# tick-mk-4_4.net
KiCad netlist of a schematic drawn in EAGLE
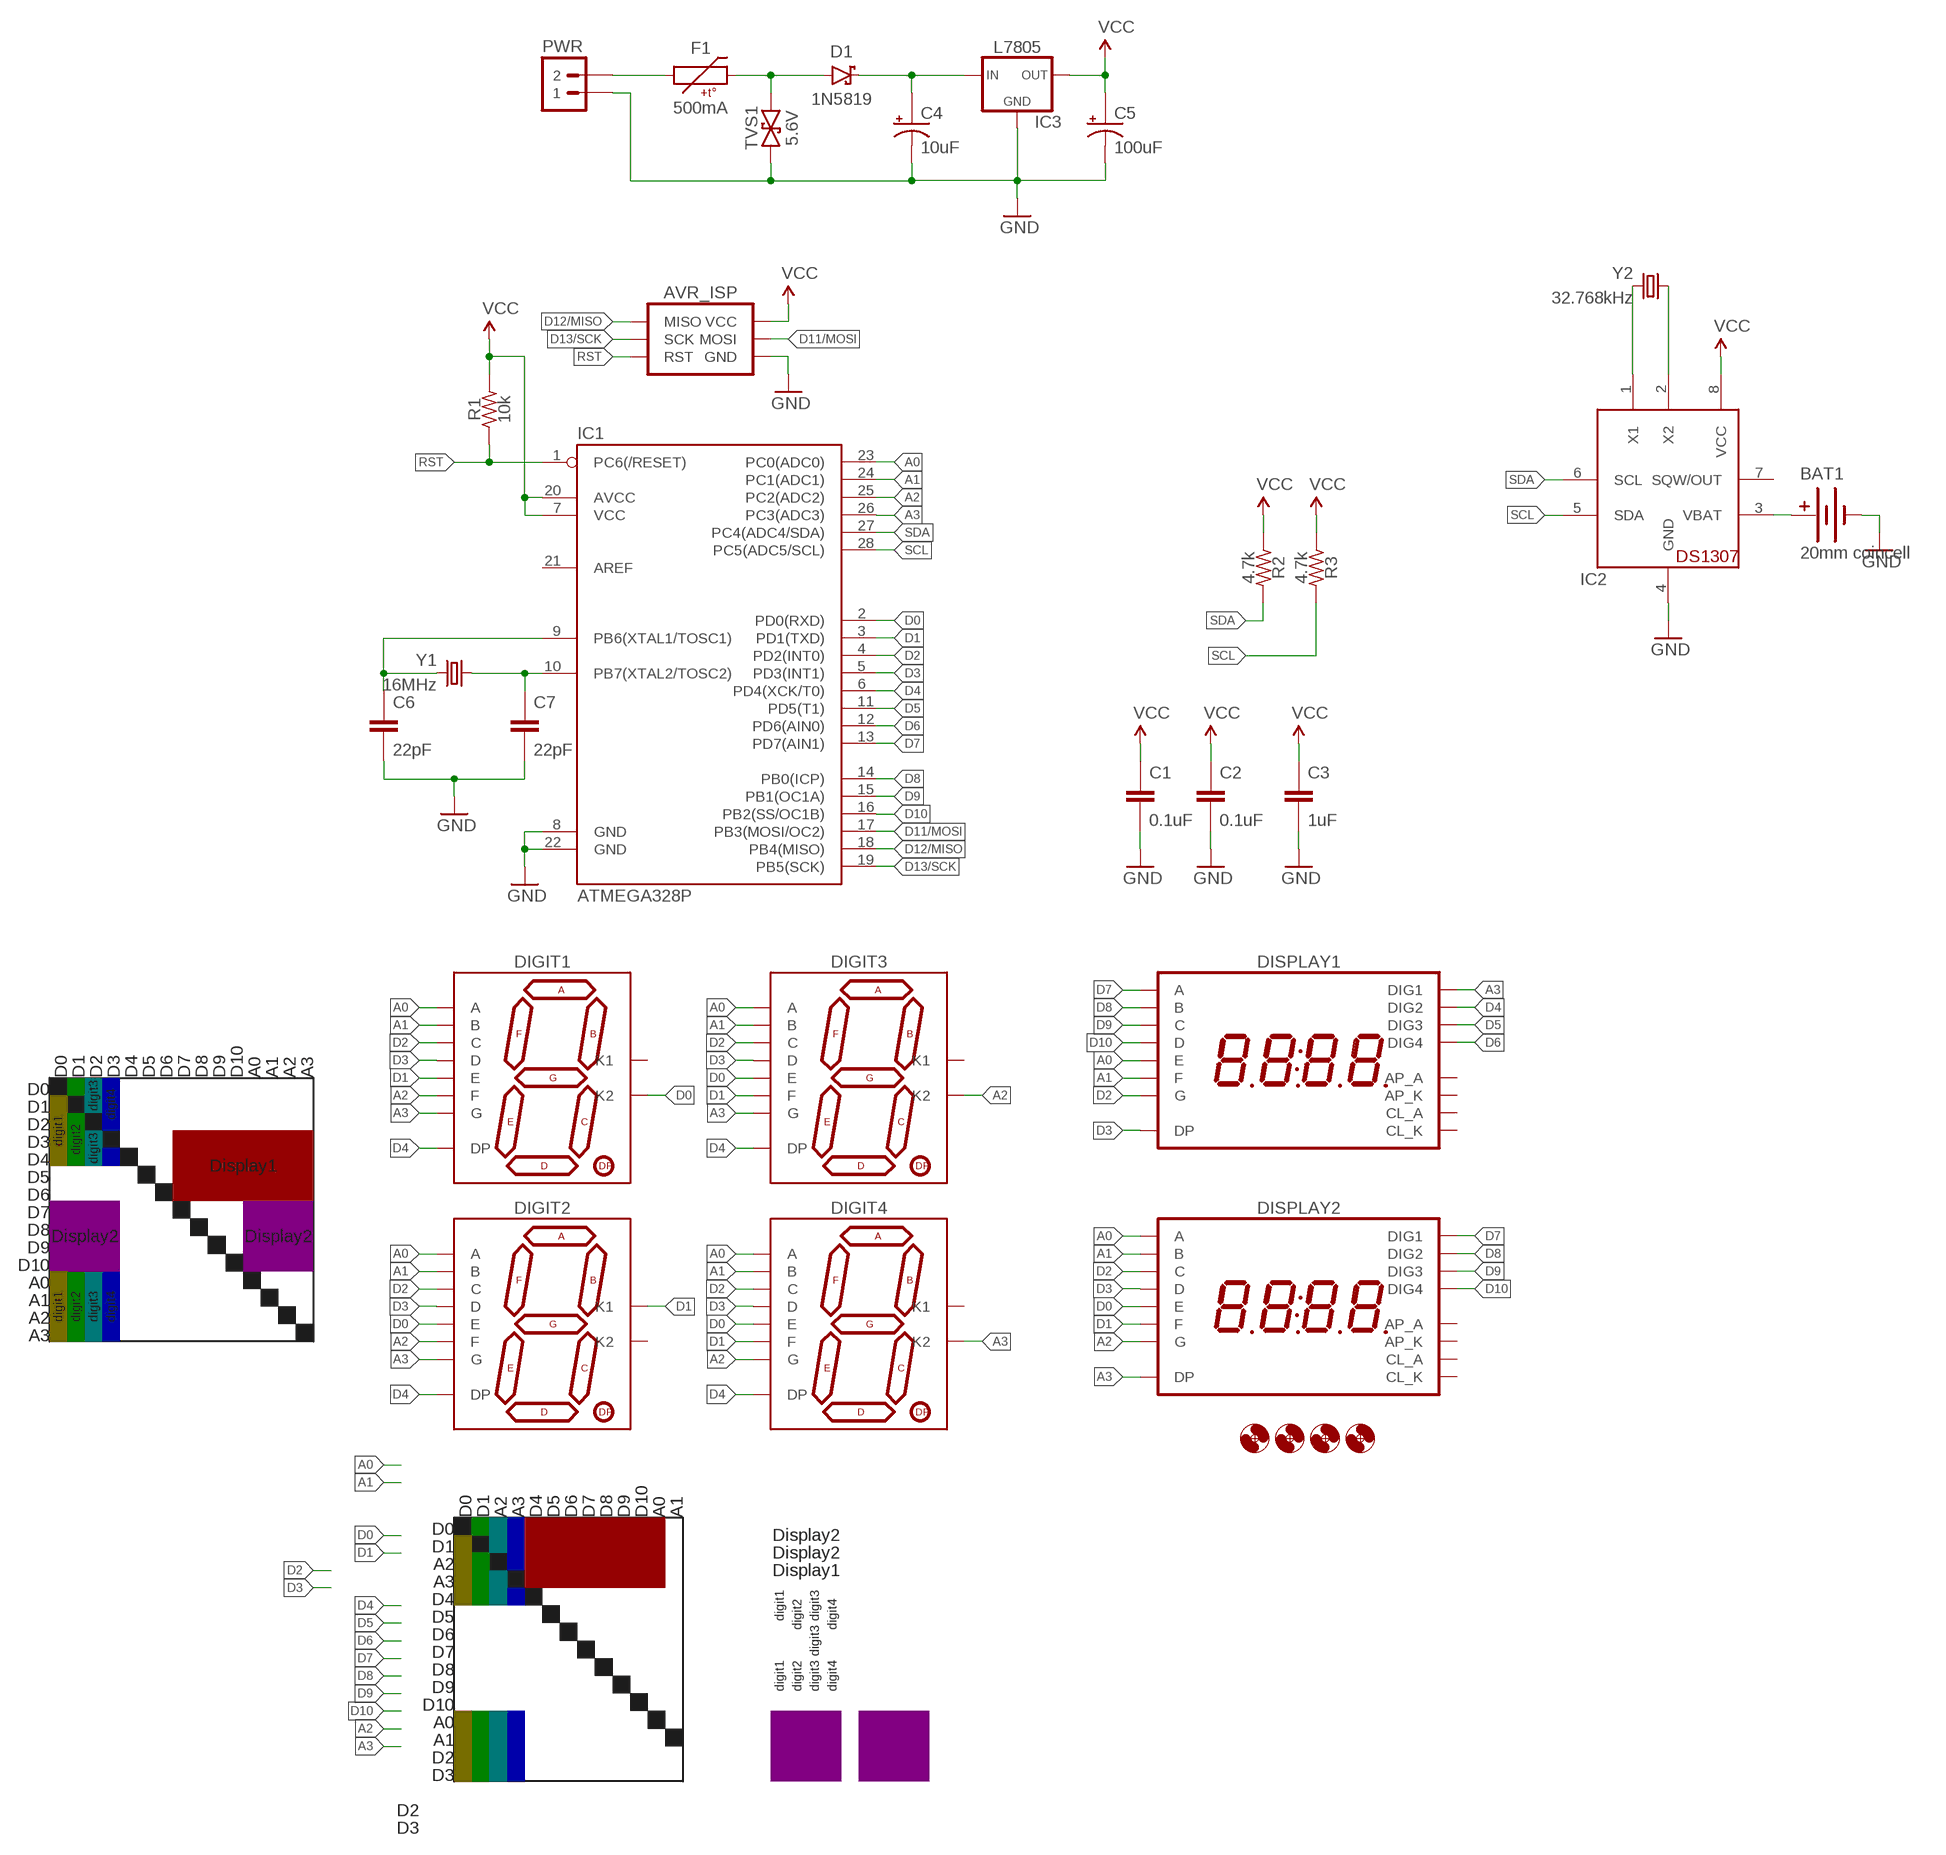
[diagram p0: schematic, sheet 1]

(export (version "E")
  (design (tool "Eeschema 10.0.6"))
  (components
    (comp (ref "AVR_ISP")
      (value "AVR_SPI_PRG_6PTH")
      (footprint "eagle-import:2X3")
      (libsource (lib "eagle-import") (part "AVR_SPI_PRG_6PTH"))
    )
    (comp (ref "BAT1")
      (value "20mm coincell")
      (footprint "eagle-import:BATTCON_20MM_MINE")
      (libsource (lib "eagle-import") (part "BATTERY20MMSMD-MINE"))
    )
    (comp (ref "C1")
      (value "0.1uF")
      (footprint "eagle-import:C025-024X044")
      (libsource (lib "eagle-import") (part "CAPACITOR-CERAMIC025-024X044"))
    )
    (comp (ref "C2")
      (value "0.1uF")
      (footprint "eagle-import:C025-024X044")
      (libsource (lib "eagle-import") (part "CAPACITOR-CERAMIC025-024X044"))
    )
    (comp (ref "C3")
      (value "1uF")
      (footprint "eagle-import:C025-024X044")
      (libsource (lib "eagle-import") (part "CAPACITOR-CERAMIC025-024X044"))
    )
    (comp (ref "C4")
      (value "10uF")
      (footprint "eagle-import:E2-5")
      (libsource (lib "eagle-import") (part "CAPACITOR-POLARIZEDE2-5"))
    )
    (comp (ref "C5")
      (value "100uF")
      (footprint "eagle-import:E2,5-6")
      (libsource (lib "eagle-import") (part "CAPACITOR-POLARIZEDE2.5-6"))
    )
    (comp (ref "C6")
      (value "22pF")
      (footprint "eagle-import:C025-024X044")
      (libsource (lib "eagle-import") (part "CAPACITOR-CERAMIC025-024X044"))
    )
    (comp (ref "C7")
      (value "22pF")
      (footprint "eagle-import:C025-024X044")
      (libsource (lib "eagle-import") (part "CAPACITOR-CERAMIC025-024X044"))
    )
    (comp (ref "D1")
      (value "1N5819")
      (footprint "eagle-import:DIODE-10.16MM")
      (libsource (lib "eagle-import") (part "DIODE-SCHOTTKYPTH-10.16MM"))
    )
    (comp (ref "DIGIT1")
      (value "7SEG_1DIGPTH-25.4MM-BARE")
      (footprint "eagle-import:7SEG_1DIG_25.4MM_NOSILK")
      (libsource (lib "eagle-import") (part "7SEG_1DIGPTH-25.4MM-BARE"))
    )
    (comp (ref "DIGIT2")
      (value "7SEG_1DIGPTH-25.4MM-BARE")
      (footprint "eagle-import:7SEG_1DIG_25.4MM_NOSILK")
      (libsource (lib "eagle-import") (part "7SEG_1DIGPTH-25.4MM-BARE"))
    )
    (comp (ref "DIGIT3")
      (value "7SEG_1DIGPTH-25.4MM-BARE")
      (footprint "eagle-import:7SEG_1DIG_25.4MM_NOSILK")
      (libsource (lib "eagle-import") (part "7SEG_1DIGPTH-25.4MM-BARE"))
    )
    (comp (ref "DIGIT4")
      (value "7SEG_1DIGPTH-25.4MM-BARE")
      (footprint "eagle-import:7SEG_1DIG_25.4MM_NOSILK")
      (libsource (lib "eagle-import") (part "7SEG_1DIGPTH-25.4MM-BARE"))
    )
    (comp (ref "DISPLAY1")
      (value "7SEG_4DIGIT_COLON_APOS")
      (footprint "eagle-import:7SEG_4DIG_10MM")
      (libsource (lib "eagle-import") (part "7SEG_4DIGIT_COLON_APOS"))
    )
    (comp (ref "DISPLAY2")
      (value "7SEG_4DIGIT_COLON_APOS")
      (footprint "eagle-import:7SEG_4DIG_10MM")
      (libsource (lib "eagle-import") (part "7SEG_4DIGIT_COLON_APOS"))
    )
    (comp (ref "F1")
      (value "500mA")
      (footprint "eagle-import:PTC-PTH-5.08MM")
      (libsource (lib "eagle-import") (part "PTCPTH-5.08MM"))
    )
    (comp (ref "H1")
      (value "HOLE#2")
      (footprint "eagle-import:HOLE-#2")
      (libsource (lib "eagle-import") (part "HOLE#2"))
    )
    (comp (ref "H2")
      (value "HOLE#2")
      (footprint "eagle-import:HOLE-#2")
      (libsource (lib "eagle-import") (part "HOLE#2"))
    )
    (comp (ref "H3")
      (value "HOLE#2")
      (footprint "eagle-import:HOLE-#2")
      (libsource (lib "eagle-import") (part "HOLE#2"))
    )
    (comp (ref "H4")
      (value "HOLE#2")
      (footprint "eagle-import:HOLE-#2")
      (libsource (lib "eagle-import") (part "HOLE#2"))
    )
    (comp (ref "IC1")
      (value "ATMEGA328P")
      (footprint "eagle-import:DIL28-3")
      (libsource (lib "eagle-import") (part "ATMEGA328P_PDIP"))
    )
    (comp (ref "IC2")
      (value "DS1307")
      (footprint "eagle-import:DIL08")
      (libsource (lib "eagle-import") (part "DS1307"))
    )
    (comp (ref "IC3")
      (value "L7805")
      (footprint "eagle-import:TO220-IGO-THERMPAD")
      (libsource (lib "eagle-import") (part "V_REG_78XXTO-220-THERMPAD"))
    )
    (comp (ref "PWR")
      (value "M02JST-PTH-VERT")
      (footprint "eagle-import:JST-2-PH-VERT-PTH")
      (libsource (lib "eagle-import") (part "M02JST-PTH-VERT"))
    )
    (comp (ref "R1")
      (value "10k")
      (footprint "eagle-import:RESISTOR-AXIAL-PTH-7.62MM")
      (libsource (lib "eagle-import") (part "RESISTORPTH-AXIAL-7.62MM"))
    )
    (comp (ref "R2")
      (value "4.7k")
      (footprint "eagle-import:RESISTOR-AXIAL-PTH-7.62MM")
      (libsource (lib "eagle-import") (part "RESISTORPTH-AXIAL-7.62MM"))
    )
    (comp (ref "R3")
      (value "4.7k")
      (footprint "eagle-import:RESISTOR-AXIAL-PTH-7.62MM")
      (libsource (lib "eagle-import") (part "RESISTORPTH-AXIAL-7.62MM"))
    )
    (comp (ref "TVS1")
      (value "5.6V")
      (footprint "eagle-import:DO-41-TVS-BI-10.16MM")
      (libsource (lib "eagle-import") (part "TVSDO-41-10.16MM"))
    )
    (comp (ref "Y1")
      (value "16MHz")
      (footprint "eagle-import:HC49U-V")
      (libsource (lib "eagle-import") (part "CRYSTALHC49UV"))
    )
    (comp (ref "Y2")
      (value "32.768kHz")
      (footprint "eagle-import:TC26H")
      (libsource (lib "eagle-import") (part "CRYSTALTC26H"))
    )
  )
  (nets
    (net (code "1") (name "A0") (class "Default")
      (node (ref "DIGIT1") (pin "7") (pinfunction "A_7") (pintype "bidirectional"))
      (node (ref "DIGIT2") (pin "7") (pinfunction "A_7") (pintype "bidirectional"))
      (node (ref "DIGIT3") (pin "7") (pinfunction "A_7") (pintype "bidirectional"))
      (node (ref "DIGIT4") (pin "7") (pinfunction "A_7") (pintype "bidirectional"))
      (node (ref "DISPLAY1") (pin "5") (pinfunction "E_5") (pintype "passive"))
      (node (ref "DISPLAY2") (pin "14") (pinfunction "A_14") (pintype "passive"))
      (node (ref "IC1") (pin "23") (pinfunction "PC0(ADC0)_23") (pintype "bidirectional"))
    )
    (net (code "2") (name "A1") (class "Default")
      (node (ref "DIGIT1") (pin "6") (pinfunction "B_6") (pintype "bidirectional"))
      (node (ref "DIGIT2") (pin "6") (pinfunction "B_6") (pintype "bidirectional"))
      (node (ref "DIGIT3") (pin "6") (pinfunction "B_6") (pintype "bidirectional"))
      (node (ref "DIGIT4") (pin "6") (pinfunction "B_6") (pintype "bidirectional"))
      (node (ref "DISPLAY1") (pin "11") (pinfunction "F_11") (pintype "passive"))
      (node (ref "DISPLAY2") (pin "16") (pinfunction "B_16") (pintype "passive"))
      (node (ref "IC1") (pin "24") (pinfunction "PC1(ADC1)_24") (pintype "bidirectional"))
    )
    (net (code "3") (name "A2") (class "Default")
      (node (ref "DIGIT1") (pin "9") (pinfunction "F_9") (pintype "bidirectional"))
      (node (ref "DIGIT2") (pin "9") (pinfunction "F_9") (pintype "bidirectional"))
      (node (ref "DIGIT3") (pin "8") (pinfunction "K2_8") (pintype "bidirectional"))
      (node (ref "DIGIT4") (pin "10") (pinfunction "G_10") (pintype "bidirectional"))
      (node (ref "DISPLAY2") (pin "15") (pinfunction "G_15") (pintype "passive"))
      (node (ref "IC1") (pin "25") (pinfunction "PC2(ADC2)_25") (pintype "bidirectional"))
    )
    (net (code "4") (name "A3") (class "Default")
      (node (ref "DIGIT1") (pin "10") (pinfunction "G_10") (pintype "bidirectional"))
      (node (ref "DIGIT2") (pin "10") (pinfunction "G_10") (pintype "bidirectional"))
      (node (ref "DIGIT3") (pin "10") (pinfunction "G_10") (pintype "bidirectional"))
      (node (ref "DIGIT4") (pin "8") (pinfunction "K2_8") (pintype "bidirectional"))
      (node (ref "DISPLAY1") (pin "1") (pinfunction "DIG1_1") (pintype "passive"))
      (node (ref "DISPLAY2") (pin "7") (pinfunction "DP_7") (pintype "passive"))
      (node (ref "IC1") (pin "26") (pinfunction "PC3(ADC3)_26") (pintype "bidirectional"))
    )
    (net (code "5") (name "D0") (class "Default")
      (node (ref "DIGIT1") (pin "8") (pinfunction "K2_8") (pintype "bidirectional"))
      (node (ref "DIGIT2") (pin "1") (pinfunction "E_1") (pintype "bidirectional"))
      (node (ref "DIGIT3") (pin "1") (pinfunction "E_1") (pintype "bidirectional"))
      (node (ref "DIGIT4") (pin "1") (pinfunction "E_1") (pintype "bidirectional"))
      (node (ref "DISPLAY2") (pin "5") (pinfunction "E_5") (pintype "passive"))
      (node (ref "IC1") (pin "2") (pinfunction "PD0(RXD)_2") (pintype "bidirectional"))
    )
    (net (code "6") (name "D1") (class "Default")
      (node (ref "DIGIT1") (pin "1") (pinfunction "E_1") (pintype "bidirectional"))
      (node (ref "DIGIT2") (pin "3") (pinfunction "K1_3") (pintype "bidirectional"))
      (node (ref "DIGIT3") (pin "9") (pinfunction "F_9") (pintype "bidirectional"))
      (node (ref "DIGIT4") (pin "9") (pinfunction "F_9") (pintype "bidirectional"))
      (node (ref "DISPLAY2") (pin "11") (pinfunction "F_11") (pintype "passive"))
      (node (ref "IC1") (pin "3") (pinfunction "PD1(TXD)_3") (pintype "bidirectional"))
    )
    (net (code "7") (name "D2") (class "Default")
      (node (ref "DIGIT1") (pin "4") (pinfunction "C_4") (pintype "bidirectional"))
      (node (ref "DIGIT2") (pin "4") (pinfunction "C_4") (pintype "bidirectional"))
      (node (ref "DIGIT3") (pin "4") (pinfunction "C_4") (pintype "bidirectional"))
      (node (ref "DIGIT4") (pin "4") (pinfunction "C_4") (pintype "bidirectional"))
      (node (ref "DISPLAY1") (pin "15") (pinfunction "G_15") (pintype "passive"))
      (node (ref "DISPLAY2") (pin "13") (pinfunction "C_13") (pintype "passive"))
      (node (ref "IC1") (pin "4") (pinfunction "PD2(INT0)_4") (pintype "bidirectional"))
    )
    (net (code "8") (name "D3") (class "Default")
      (node (ref "DIGIT1") (pin "2") (pinfunction "D_2") (pintype "bidirectional"))
      (node (ref "DIGIT2") (pin "2") (pinfunction "D_2") (pintype "bidirectional"))
      (node (ref "DIGIT3") (pin "2") (pinfunction "D_2") (pintype "bidirectional"))
      (node (ref "DIGIT4") (pin "2") (pinfunction "D_2") (pintype "bidirectional"))
      (node (ref "DISPLAY1") (pin "7") (pinfunction "DP_7") (pintype "passive"))
      (node (ref "DISPLAY2") (pin "3") (pinfunction "D_3") (pintype "passive"))
      (node (ref "IC1") (pin "5") (pinfunction "PD3(INT1)_5") (pintype "bidirectional"))
    )
    (net (code "9") (name "D4") (class "Default")
      (node (ref "DIGIT1") (pin "5") (pinfunction "DP_5") (pintype "bidirectional"))
      (node (ref "DIGIT2") (pin "5") (pinfunction "DP_5") (pintype "bidirectional"))
      (node (ref "DIGIT3") (pin "5") (pinfunction "DP_5") (pintype "bidirectional"))
      (node (ref "DIGIT4") (pin "5") (pinfunction "DP_5") (pintype "bidirectional"))
      (node (ref "DISPLAY1") (pin "2") (pinfunction "DIG2_2") (pintype "passive"))
      (node (ref "IC1") (pin "6") (pinfunction "PD4(XCK/T0)_6") (pintype "bidirectional"))
    )
    (net (code "10") (name "D5") (class "Default")
      (node (ref "DISPLAY1") (pin "6") (pinfunction "DIG3_6") (pintype "passive"))
      (node (ref "IC1") (pin "11") (pinfunction "PD5(T1)_11") (pintype "bidirectional"))
    )
    (net (code "11") (name "D6") (class "Default")
      (node (ref "DISPLAY1") (pin "8") (pinfunction "DIG4_8") (pintype "passive"))
      (node (ref "IC1") (pin "12") (pinfunction "PD6(AIN0)_12") (pintype "bidirectional"))
    )
    (net (code "12") (name "D7") (class "Default")
      (node (ref "DISPLAY1") (pin "14") (pinfunction "A_14") (pintype "passive"))
      (node (ref "DISPLAY2") (pin "1") (pinfunction "DIG1_1") (pintype "passive"))
      (node (ref "IC1") (pin "13") (pinfunction "PD7(AIN1)_13") (pintype "bidirectional"))
    )
    (net (code "13") (name "D8") (class "Default")
      (node (ref "DISPLAY1") (pin "16") (pinfunction "B_16") (pintype "passive"))
      (node (ref "DISPLAY2") (pin "2") (pinfunction "DIG2_2") (pintype "passive"))
      (node (ref "IC1") (pin "14") (pinfunction "PB0(ICP)_14") (pintype "bidirectional"))
    )
    (net (code "14") (name "D9") (class "Default")
      (node (ref "DISPLAY1") (pin "13") (pinfunction "C_13") (pintype "passive"))
      (node (ref "DISPLAY2") (pin "6") (pinfunction "DIG3_6") (pintype "passive"))
      (node (ref "IC1") (pin "15") (pinfunction "PB1(OC1A)_15") (pintype "bidirectional"))
    )
    (net (code "15") (name "D10") (class "Default")
      (node (ref "DISPLAY1") (pin "3") (pinfunction "D_3") (pintype "passive"))
      (node (ref "DISPLAY2") (pin "8") (pinfunction "DIG4_8") (pintype "passive"))
      (node (ref "IC1") (pin "16") (pinfunction "PB2(SS/OC1B)_16") (pintype "bidirectional"))
    )
    (net (code "16") (name "D11{slash}MOSI") (class "Default")
      (node (ref "AVR_ISP") (pin "4") (pinfunction "MOSI_4") (pintype "passive"))
      (node (ref "IC1") (pin "17") (pinfunction "PB3(MOSI/OC2)_17") (pintype "bidirectional"))
    )
    (net (code "17") (name "D12{slash}MISO") (class "Default")
      (node (ref "AVR_ISP") (pin "1") (pinfunction "MISO_1") (pintype "passive"))
      (node (ref "IC1") (pin "18") (pinfunction "PB4(MISO)_18") (pintype "bidirectional"))
    )
    (net (code "18") (name "D13{slash}SCK") (class "Default")
      (node (ref "AVR_ISP") (pin "3") (pinfunction "SCK_3") (pintype "passive"))
      (node (ref "IC1") (pin "19") (pinfunction "PB5(SCK)_19") (pintype "bidirectional"))
    )
    (net (code "19") (name "GND") (class "Default")
      (node (ref "AVR_ISP") (pin "6") (pinfunction "GND_6") (pintype "passive"))
      (node (ref "BAT1") (pin "BOTTOM") (pinfunction "-_BOTTOM") (pintype "power_in"))
      (node (ref "C1") (pin "2") (pinfunction "2_2") (pintype "passive"))
      (node (ref "C2") (pin "2") (pinfunction "2_2") (pintype "passive"))
      (node (ref "C3") (pin "2") (pinfunction "2_2") (pintype "passive"))
      (node (ref "C4") (pin "-") (pinfunction "-_-") (pintype "passive"))
      (node (ref "C5") (pin "-") (pinfunction "-_-") (pintype "passive"))
      (node (ref "C6") (pin "2") (pinfunction "2_2") (pintype "passive"))
      (node (ref "C7") (pin "2") (pinfunction "2_2") (pintype "passive"))
      (node (ref "IC1") (pin "22") (pinfunction "GND_22") (pintype "bidirectional"))
      (node (ref "IC1") (pin "8") (pinfunction "GND_8") (pintype "bidirectional"))
      (node (ref "IC2") (pin "4") (pinfunction "GND_4") (pintype "power_in"))
      (node (ref "IC3") (pin "4") (pinfunction "GND_4") (pintype "bidirectional"))
      (node (ref "IC3") (pin "GND") (pinfunction "GND_GND") (pintype "bidirectional"))
      (node (ref "PWR") (pin "1") (pinfunction "1_1") (pintype "passive"))
      (node (ref "TVS1") (pin "P$1") (pinfunction "1_P$1") (pintype "passive"))
    )
    (net (code "20") (name "Net-(C4-Pad+)") (class "Default")
      (node (ref "C4") (pin "+") (pinfunction "+_+") (pintype "passive"))
      (node (ref "D1") (pin "C") (pinfunction "C_C") (pintype "passive"))
      (node (ref "IC3") (pin "IN") (pinfunction "IN_IN") (pintype "bidirectional"))
    )
    (net (code "21") (name "Net-(F1-1)") (class "Default")
      (node (ref "F1") (pin "P$1") (pinfunction "1_P$1") (pintype "passive"))
      (node (ref "PWR") (pin "2") (pinfunction "2_2") (pintype "passive"))
    )
    (net (code "22") (name "Net-(F1-2)") (class "Default")
      (node (ref "D1") (pin "A") (pinfunction "A_A") (pintype "passive"))
      (node (ref "F1") (pin "P$2") (pinfunction "2_P$2") (pintype "passive"))
      (node (ref "TVS1") (pin "P$2") (pinfunction "2_P$2") (pintype "passive"))
    )
    (net (code "23") (name "Net-(IC1-PB6(XTAL1{slash}TOSC1))") (class "Default")
      (node (ref "C6") (pin "1") (pinfunction "1_1") (pintype "passive"))
      (node (ref "IC1") (pin "9") (pinfunction "PB6(XTAL1/TOSC1)_9") (pintype "bidirectional"))
      (node (ref "Y1") (pin "2") (pinfunction "2_2") (pintype "passive"))
    )
    (net (code "24") (name "Net-(IC1-PB7(XTAL2{slash}TOSC2))") (class "Default")
      (node (ref "C7") (pin "1") (pinfunction "1_1") (pintype "passive"))
      (node (ref "IC1") (pin "10") (pinfunction "PB7(XTAL2/TOSC2)_10") (pintype "bidirectional"))
      (node (ref "Y1") (pin "1") (pinfunction "1_1") (pintype "passive"))
    )
    (net (code "25") (name "Net-(IC2-VBAT)") (class "Default")
      (node (ref "BAT1") (pin "TOP@1") (pinfunction "+_TOP@1") (pintype "power_in"))
      (node (ref "BAT1") (pin "TOP@2") (pinfunction "+_TOP@2") (pintype "power_in"))
      (node (ref "IC2") (pin "3") (pinfunction "VBAT_3") (pintype "power_in"))
    )
    (net (code "26") (name "Net-(IC2-X1)") (class "Default")
      (node (ref "IC2") (pin "1") (pinfunction "X1_1") (pintype "passive"))
      (node (ref "Y2") (pin "2") (pinfunction "2_2") (pintype "passive"))
    )
    (net (code "27") (name "Net-(IC2-X2)") (class "Default")
      (node (ref "IC2") (pin "2") (pinfunction "X2_2") (pintype "passive"))
      (node (ref "Y2") (pin "1") (pinfunction "1_1") (pintype "passive"))
    )
    (net (code "28") (name "RST") (class "Default")
      (node (ref "AVR_ISP") (pin "5") (pinfunction "RST_5") (pintype "passive"))
      (node (ref "IC1") (pin "1") (pinfunction "PC6(/RESET)_1") (pintype "bidirectional"))
      (node (ref "R1") (pin "P$1") (pinfunction "1_P$1") (pintype "passive"))
    )
    (net (code "29") (name "SCL") (class "Default")
      (node (ref "IC1") (pin "28") (pinfunction "PC5(ADC5/SCL)_28") (pintype "bidirectional"))
      (node (ref "IC2") (pin "5") (pinfunction "SDA_5") (pintype "bidirectional"))
      (node (ref "R3") (pin "P$2") (pinfunction "2_P$2") (pintype "passive"))
    )
    (net (code "30") (name "SDA") (class "Default")
      (node (ref "IC1") (pin "27") (pinfunction "PC4(ADC4/SDA)_27") (pintype "bidirectional"))
      (node (ref "IC2") (pin "6") (pinfunction "SCL_6") (pintype "bidirectional"))
      (node (ref "R2") (pin "P$2") (pinfunction "2_P$2") (pintype "passive"))
    )
    (net (code "31") (name "VCC") (class "Default")
      (node (ref "AVR_ISP") (pin "2") (pinfunction "VCC_2") (pintype "passive"))
      (node (ref "C1") (pin "1") (pinfunction "1_1") (pintype "passive"))
      (node (ref "C2") (pin "1") (pinfunction "1_1") (pintype "passive"))
      (node (ref "C3") (pin "1") (pinfunction "1_1") (pintype "passive"))
      (node (ref "C5") (pin "+") (pinfunction "+_+") (pintype "passive"))
      (node (ref "IC1") (pin "20") (pinfunction "AVCC_20") (pintype "bidirectional"))
      (node (ref "IC1") (pin "7") (pinfunction "VCC_7") (pintype "bidirectional"))
      (node (ref "IC2") (pin "8") (pinfunction "VCC_8") (pintype "power_in"))
      (node (ref "IC3") (pin "OUT") (pinfunction "OUT_OUT") (pintype "bidirectional"))
      (node (ref "R1") (pin "P$2") (pinfunction "2_P$2") (pintype "passive"))
      (node (ref "R2") (pin "P$1") (pinfunction "1_P$1") (pintype "passive"))
      (node (ref "R3") (pin "P$1") (pinfunction "1_P$1") (pintype "passive"))
    )
    (net (code "32") (name "unconnected-(DIGIT1-K1-Pad3)") (class "Default")
      (node (ref "DIGIT1") (pin "3") (pinfunction "K1_3") (pintype "bidirectional"))
    )
    (net (code "33") (name "unconnected-(DIGIT2-K2-Pad8)") (class "Default")
      (node (ref "DIGIT2") (pin "8") (pinfunction "K2_8") (pintype "bidirectional"))
    )
    (net (code "34") (name "unconnected-(DIGIT3-K1-Pad3)") (class "Default")
      (node (ref "DIGIT3") (pin "3") (pinfunction "K1_3") (pintype "bidirectional"))
    )
    (net (code "35") (name "unconnected-(DIGIT4-K1-Pad3)") (class "Default")
      (node (ref "DIGIT4") (pin "3") (pinfunction "K1_3") (pintype "bidirectional"))
    )
    (net (code "36") (name "unconnected-(DISPLAY1-AP_A-Pad10)") (class "Default")
      (node (ref "DISPLAY1") (pin "10") (pinfunction "AP_A_10") (pintype "bidirectional"))
    )
    (net (code "37") (name "unconnected-(DISPLAY1-AP_K-Pad9)") (class "Default")
      (node (ref "DISPLAY1") (pin "9") (pinfunction "AP_K_9") (pintype "bidirectional"))
    )
    (net (code "38") (name "unconnected-(DISPLAY1-CL_A-Pad4)") (class "Default")
      (node (ref "DISPLAY1") (pin "4") (pinfunction "CL_A_4") (pintype "passive"))
    )
    (net (code "39") (name "unconnected-(DISPLAY1-CL_K-Pad12)") (class "Default")
      (node (ref "DISPLAY1") (pin "12") (pinfunction "CL_K_12") (pintype "passive"))
    )
    (net (code "40") (name "unconnected-(DISPLAY2-AP_A-Pad10)") (class "Default")
      (node (ref "DISPLAY2") (pin "10") (pinfunction "AP_A_10") (pintype "bidirectional"))
    )
    (net (code "41") (name "unconnected-(DISPLAY2-AP_K-Pad9)") (class "Default")
      (node (ref "DISPLAY2") (pin "9") (pinfunction "AP_K_9") (pintype "bidirectional"))
    )
    (net (code "42") (name "unconnected-(DISPLAY2-CL_A-Pad4)") (class "Default")
      (node (ref "DISPLAY2") (pin "4") (pinfunction "CL_A_4") (pintype "passive"))
    )
    (net (code "43") (name "unconnected-(DISPLAY2-CL_K-Pad12)") (class "Default")
      (node (ref "DISPLAY2") (pin "12") (pinfunction "CL_K_12") (pintype "passive"))
    )
    (net (code "44") (name "unconnected-(IC1-AREF-Pad21)") (class "Default")
      (node (ref "IC1") (pin "21") (pinfunction "AREF_21") (pintype "bidirectional"))
    )
    (net (code "45") (name "unconnected-(IC2-SQW{slash}OUT-Pad7)") (class "Default")
      (node (ref "IC2") (pin "7") (pinfunction "SQW/OUT_7") (pintype "bidirectional"))
    )
  )
)
